# XMOS_power.net
KiCad netlist of a schematic drawn in Altium Designer
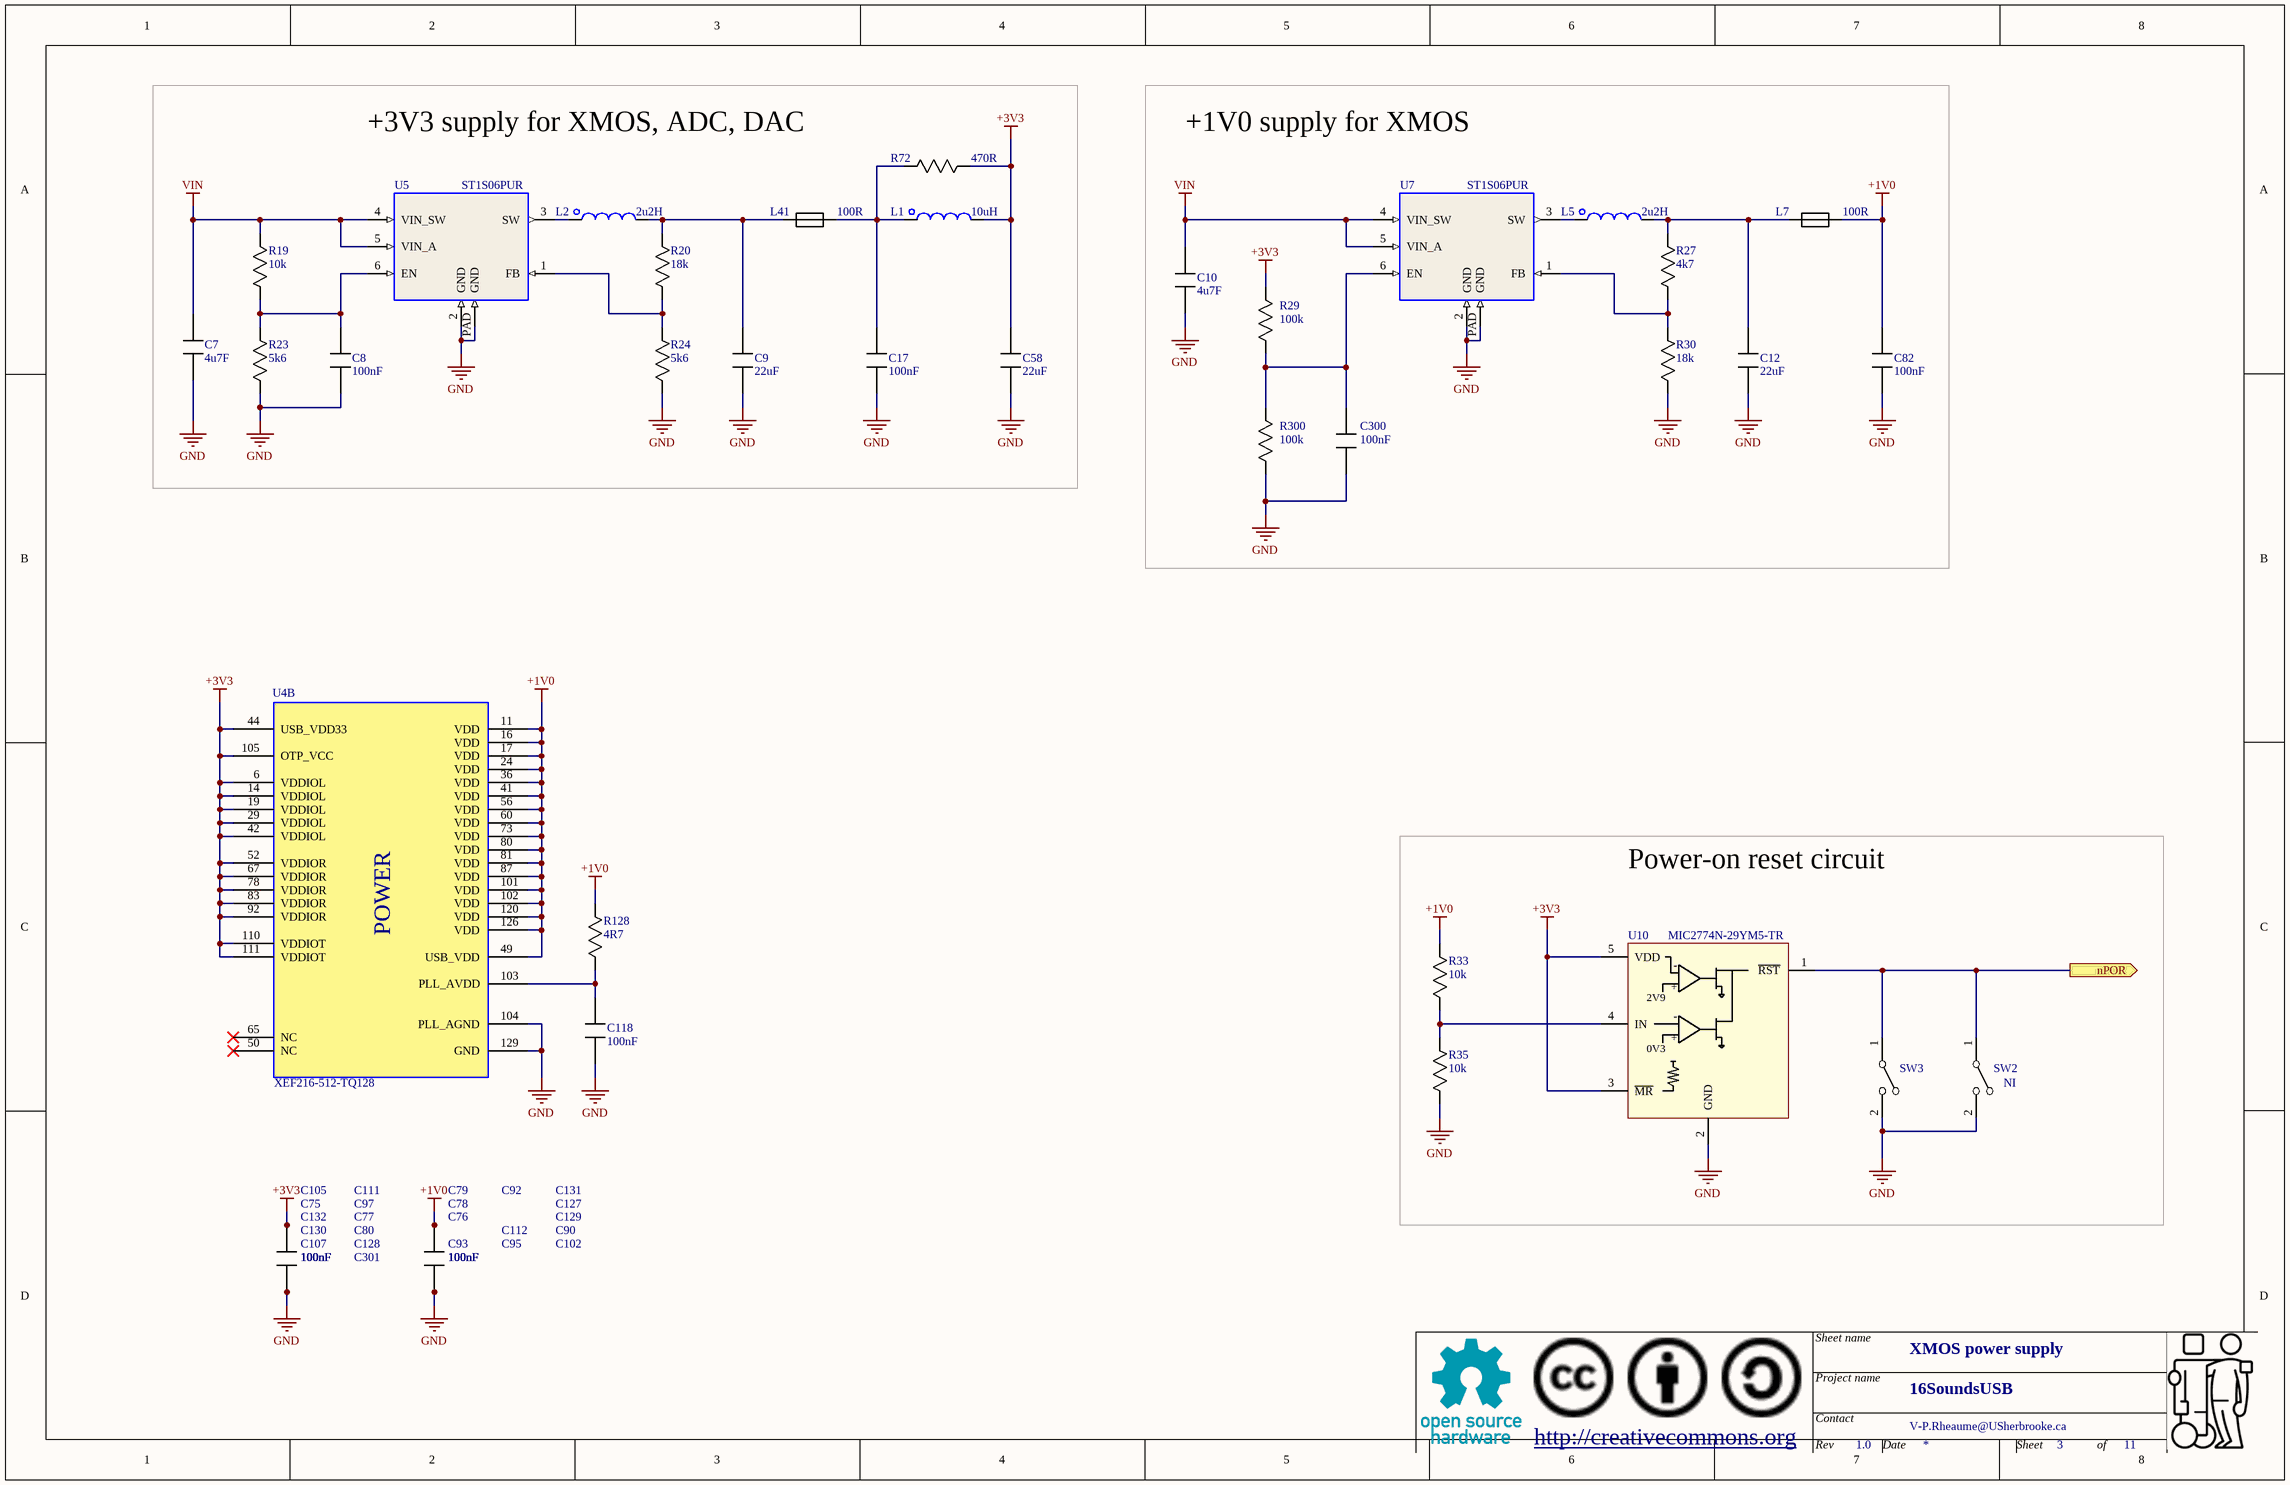
[diagram p0: XMOS_power.SchDoc]

(export (version "E")
  (design (tool "Eeschema 10.0.6"))
  (components
    (comp (ref "C7")
      (value "4u7F")
      (footprint "0805")
      (description "Capacitor")
      (libsource (lib "INTER_2014") (part "Capacitor"))
    )
    (comp (ref "C8")
      (value "100nF")
      (footprint "0603")
      (description "Capacitor")
      (libsource (lib "INTER_2014") (part "Capacitor"))
    )
    (comp (ref "C9")
      (value "22uF")
      (footprint "1206")
      (description "Capacitor")
      (libsource (lib "INTER_2014") (part "Capacitor"))
    )
    (comp (ref "C10")
      (value "4u7F")
      (footprint "0805")
      (description "Capacitor")
      (libsource (lib "INTER_2014") (part "Capacitor"))
    )
    (comp (ref "C12")
      (value "22uF")
      (footprint "1206")
      (description "Capacitor")
      (libsource (lib "INTER_2014") (part "Capacitor"))
    )
    (comp (ref "C17")
      (value "100nF")
      (footprint "0603")
      (description "Capacitor")
      (libsource (lib "INTER_2014") (part "Capacitor"))
    )
    (comp (ref "C58")
      (value "22uF")
      (footprint "1206")
      (description "Capacitor")
      (libsource (lib "INTER_2014") (part "Capacitor"))
    )
    (comp (ref "C75")
      (value "100nF")
      (footprint "0603")
      (description "Capacitor")
      (libsource (lib "INTER_2014") (part "Capacitor"))
    )
    (comp (ref "C76")
      (value "100nF")
      (footprint "0603")
      (description "Capacitor")
      (libsource (lib "INTER_2014") (part "Capacitor"))
    )
    (comp (ref "C77")
      (value "100nF")
      (footprint "0603")
      (description "Capacitor")
      (libsource (lib "INTER_2014") (part "Capacitor"))
    )
    (comp (ref "C78")
      (value "100nF")
      (footprint "0603")
      (description "Capacitor")
      (libsource (lib "INTER_2014") (part "Capacitor"))
    )
    (comp (ref "C79")
      (value "100nF")
      (footprint "0603")
      (description "Capacitor")
      (libsource (lib "INTER_2014") (part "Capacitor"))
    )
    (comp (ref "C80")
      (value "100nF")
      (footprint "0603")
      (description "Capacitor")
      (libsource (lib "INTER_2014") (part "Capacitor"))
    )
    (comp (ref "C82")
      (value "100nF")
      (footprint "0603")
      (description "Capacitor")
      (libsource (lib "INTER_2014") (part "Capacitor"))
    )
    (comp (ref "C90")
      (value "100nF")
      (footprint "0603")
      (description "Capacitor")
      (libsource (lib "INTER_2014") (part "Capacitor"))
    )
    (comp (ref "C92")
      (value "100nF")
      (footprint "0603")
      (description "Capacitor")
      (libsource (lib "INTER_2014") (part "Capacitor"))
    )
    (comp (ref "C93")
      (value "100nF")
      (footprint "0603")
      (description "Capacitor")
      (libsource (lib "INTER_2014") (part "Capacitor"))
    )
    (comp (ref "C95")
      (value "100nF")
      (footprint "0603")
      (description "Capacitor")
      (libsource (lib "INTER_2014") (part "Capacitor"))
    )
    (comp (ref "C97")
      (value "100nF")
      (footprint "0603")
      (description "Capacitor")
      (libsource (lib "INTER_2014") (part "Capacitor"))
    )
    (comp (ref "C102")
      (value "100nF")
      (footprint "0603")
      (description "Capacitor")
      (libsource (lib "INTER_2014") (part "Capacitor"))
    )
    (comp (ref "C105")
      (value "100nF")
      (footprint "0603")
      (description "Capacitor")
      (libsource (lib "INTER_2014") (part "Capacitor"))
    )
    (comp (ref "C107")
      (value "100nF")
      (footprint "0603")
      (description "Capacitor")
      (libsource (lib "INTER_2014") (part "Capacitor"))
    )
    (comp (ref "C111")
      (value "100nF")
      (footprint "0603")
      (description "Capacitor")
      (libsource (lib "INTER_2014") (part "Capacitor"))
    )
    (comp (ref "C112")
      (value "100nF")
      (footprint "0603")
      (description "Capacitor")
      (libsource (lib "INTER_2014") (part "Capacitor"))
    )
    (comp (ref "C118")
      (value "100nF")
      (footprint "0603")
      (description "Capacitor")
      (libsource (lib "INTER_2014") (part "Capacitor"))
    )
    (comp (ref "C127")
      (value "100nF")
      (footprint "0603")
      (description "Capacitor")
      (libsource (lib "INTER_2014") (part "Capacitor"))
    )
    (comp (ref "C128")
      (value "100nF")
      (footprint "0603")
      (description "Capacitor")
      (libsource (lib "INTER_2014") (part "Capacitor"))
    )
    (comp (ref "C129")
      (value "100nF")
      (footprint "0603")
      (description "Capacitor")
      (libsource (lib "INTER_2014") (part "Capacitor"))
    )
    (comp (ref "C130")
      (value "100nF")
      (footprint "0603")
      (description "Capacitor")
      (libsource (lib "INTER_2014") (part "Capacitor"))
    )
    (comp (ref "C131")
      (value "100nF")
      (footprint "0603")
      (description "Capacitor")
      (libsource (lib "INTER_2014") (part "Capacitor"))
    )
    (comp (ref "C132")
      (value "100nF")
      (footprint "0603")
      (description "Capacitor")
      (libsource (lib "INTER_2014") (part "Capacitor"))
    )
    (comp (ref "C300")
      (value "100nF")
      (footprint "0603")
      (description "Capacitor")
      (libsource (lib "INTER_2014") (part "Capacitor"))
    )
    (comp (ref "C301")
      (value "100nF")
      (footprint "0603")
      (description "Capacitor")
      (libsource (lib "INTER_2014") (part "Capacitor"))
    )
    (comp (ref "L1")
      (value "10uH")
      (footprint "IND_252012CDMC/DS")
      (description "Inductor")
      (fields (field (name "MFG") "Murata"))
      (libsource (lib "INTER_2014") (part "Inductor"))
    )
    (comp (ref "L2")
      (value "2u2H")
      (footprint "IND_252012CDMC/DS")
      (description "Inductor")
      (fields (field (name "MFG") "Murata"))
      (libsource (lib "INTER_2014") (part "Inductor"))
    )
    (comp (ref "L5")
      (value "2u2H")
      (footprint "IND_252012CDMC/DS")
      (description "Inductor")
      (fields (field (name "MFG") "Murata"))
      (libsource (lib "INTER_2014") (part "Inductor"))
    )
    (comp (ref "L7")
      (value "100R")
      (footprint "0805")
      (description "Ferrite")
      (libsource (lib "INTER_2014") (part "Ferrite"))
    )
    (comp (ref "L41")
      (value "100R")
      (footprint "0805")
      (description "Ferrite")
      (libsource (lib "INTER_2014") (part "Ferrite"))
    )
    (comp (ref "R19")
      (value "10k")
      (footprint "0603")
      (description "Resistor")
      (libsource (lib "INTER_2014") (part "Resistor"))
    )
    (comp (ref "R20")
      (value "18k")
      (footprint "0603")
      (description "Resistor")
      (libsource (lib "INTER_2014") (part "Resistor"))
    )
    (comp (ref "R23")
      (value "5k6")
      (footprint "0603")
      (description "Resistor")
      (libsource (lib "INTER_2014") (part "Resistor"))
    )
    (comp (ref "R24")
      (value "5k6")
      (footprint "0603")
      (description "Resistor")
      (libsource (lib "INTER_2014") (part "Resistor"))
    )
    (comp (ref "R27")
      (value "4k7")
      (footprint "0603")
      (description "Resistor")
      (libsource (lib "INTER_2014") (part "Resistor"))
    )
    (comp (ref "R29")
      (value "100k")
      (footprint "0603")
      (description "Resistor")
      (libsource (lib "INTER_2014") (part "Resistor"))
    )
    (comp (ref "R30")
      (value "18k")
      (footprint "0603")
      (description "Resistor")
      (libsource (lib "INTER_2014") (part "Resistor"))
    )
    (comp (ref "R33")
      (value "10k")
      (footprint "0603")
      (description "Resistor")
      (libsource (lib "INTER_2014") (part "Resistor"))
    )
    (comp (ref "R35")
      (value "10k")
      (footprint "0603")
      (description "Resistor")
      (libsource (lib "INTER_2014") (part "Resistor"))
    )
    (comp (ref "R72")
      (value "470R")
      (footprint "0603")
      (description "Resistor")
      (libsource (lib "INTER_2014") (part "Resistor"))
    )
    (comp (ref "R128")
      (value "4R7")
      (footprint "0603")
      (description "Resistor")
      (libsource (lib "INTER_2014") (part "Resistor"))
    )
    (comp (ref "R300")
      (value "100k")
      (footprint "0603")
      (description "Resistor")
      (libsource (lib "INTER_2014") (part "Resistor"))
    )
    (comp (ref "SW2")
      (value "Button")
      (footprint "BUTTON_WS-TASV")
      (fields (field (name "MFG") "Wurth") (field (name "NI") "NI"))
      (libsource (lib "INTER_2014") (part "Button"))
    )
    (comp (ref "SW3")
      (value "Button")
      (footprint "BUTTON_WS-TASV")
      (fields (field (name "MFG") "Wurth"))
      (libsource (lib "INTER_2014") (part "Button"))
    )
    (comp (ref "U4")
      (value "~")
      (footprint "TQFP128_XMOS")
      (description "32-bit multicore microcontroller. 2 Tiles. 16 Logical Cores. 512KB SRAM. 1000MIPS. TQFP128.")
      (fields (field (name "MFG") "XMOS") (field (name "MFG_PN") "XEF216-512-TQ128"))
      (libsource (lib "INTER_2014") (part "XMOS_XEF216-512-TQ128"))
    )
    (comp (ref "U5")
      (value "ST1S06PUR")
      (footprint "DFN6_ST1S06")
      (description "DC-DC Buck Converter, 1.5A, 1.5MHz, DFN6")
      (fields (field (name "MFG") "ST Microelectronics") (field (name "MFG_PN") "ST1S06PUR"))
      (libsource (lib "INTER_2014") (part "ST1S06PUR"))
    )
    (comp (ref "U7")
      (value "ST1S06PUR")
      (footprint "DFN6_ST1S06")
      (description "DC-DC Buck Converter, 1.5A, 1.5MHz, DFN6")
      (fields (field (name "MFG") "ST Microelectronics") (field (name "MFG_PN") "ST1S06PUR"))
      (libsource (lib "INTER_2014") (part "ST1S06PUR"))
    )
    (comp (ref "U10")
      (value "MIC2774N-29YM5-TR")
      (footprint "SOT23_5")
      (description "Voltage supervisor and power-on timer, dual")
      (fields (field (name "MFG") "Micrel"))
      (libsource (lib "INTER_2014") (part "MIC2774N-29YM5-TR"))
    )
  )
  (nets
    (net (code "1") (name "+1V0") (class "Default")
      (node (ref "C102") (pin "1") (pintype "passive"))
      (node (ref "C112") (pin "1") (pintype "passive"))
      (node (ref "C127") (pin "1") (pintype "passive"))
      (node (ref "C129") (pin "1") (pintype "passive"))
      (node (ref "C131") (pin "1") (pintype "passive"))
      (node (ref "C76") (pin "1") (pintype "passive"))
      (node (ref "C78") (pin "1") (pintype "passive"))
      (node (ref "C79") (pin "1") (pintype "passive"))
      (node (ref "C82") (pin "1") (pintype "passive"))
      (node (ref "C90") (pin "1") (pintype "passive"))
      (node (ref "C92") (pin "1") (pintype "passive"))
      (node (ref "C93") (pin "1") (pintype "passive"))
      (node (ref "C95") (pin "1") (pintype "passive"))
      (node (ref "L7") (pin "2") (pintype "passive"))
      (node (ref "R128") (pin "1") (pintype "passive"))
      (node (ref "R33") (pin "1") (pintype "passive"))
      (node (ref "U4") (pin "101") (pinfunction "VDD_101") (pintype "power_in"))
      (node (ref "U4") (pin "102") (pinfunction "VDD_102") (pintype "power_in"))
      (node (ref "U4") (pin "11") (pinfunction "VDD_11") (pintype "power_in"))
      (node (ref "U4") (pin "120") (pinfunction "VDD_120") (pintype "power_in"))
      (node (ref "U4") (pin "126") (pinfunction "VDD_126") (pintype "power_in"))
      (node (ref "U4") (pin "16") (pinfunction "VDD_16") (pintype "power_in"))
      (node (ref "U4") (pin "17") (pinfunction "VDD_17") (pintype "power_in"))
      (node (ref "U4") (pin "24") (pinfunction "VDD_24") (pintype "power_in"))
      (node (ref "U4") (pin "36") (pinfunction "VDD_36") (pintype "power_in"))
      (node (ref "U4") (pin "41") (pinfunction "VDD_41") (pintype "power_in"))
      (node (ref "U4") (pin "49") (pinfunction "USB_VDD_49") (pintype "power_in"))
      (node (ref "U4") (pin "56") (pinfunction "VDD_56") (pintype "power_in"))
      (node (ref "U4") (pin "60") (pinfunction "VDD_60") (pintype "power_in"))
      (node (ref "U4") (pin "73") (pinfunction "VDD_73") (pintype "power_in"))
      (node (ref "U4") (pin "80") (pinfunction "VDD_80") (pintype "power_in"))
      (node (ref "U4") (pin "81") (pinfunction "VDD_81") (pintype "power_in"))
      (node (ref "U4") (pin "87") (pinfunction "VDD_87") (pintype "power_in"))
    )
    (net (code "2") (name "+3V3") (class "Default")
      (node (ref "C105") (pin "1") (pintype "passive"))
      (node (ref "C107") (pin "1") (pintype "passive"))
      (node (ref "C111") (pin "1") (pintype "passive"))
      (node (ref "C128") (pin "1") (pintype "passive"))
      (node (ref "C130") (pin "1") (pintype "passive"))
      (node (ref "C132") (pin "1") (pintype "passive"))
      (node (ref "C301") (pin "1") (pintype "passive"))
      (node (ref "C58") (pin "1") (pintype "passive"))
      (node (ref "C75") (pin "1") (pintype "passive"))
      (node (ref "C77") (pin "1") (pintype "passive"))
      (node (ref "C80") (pin "1") (pintype "passive"))
      (node (ref "C97") (pin "1") (pintype "passive"))
      (node (ref "L1") (pin "2") (pintype "passive"))
      (node (ref "R29") (pin "1") (pintype "passive"))
      (node (ref "R72") (pin "1") (pintype "passive"))
      (node (ref "U10") (pin "3") (pinfunction "~{MR}_3") (pintype "passive"))
      (node (ref "U10") (pin "5") (pinfunction "VDD_5") (pintype "passive"))
      (node (ref "U4") (pin "105") (pinfunction "OTP_VCC_105") (pintype "power_in"))
      (node (ref "U4") (pin "110") (pinfunction "VDDIOT_110") (pintype "power_in"))
      (node (ref "U4") (pin "111") (pinfunction "VDDIOT_111") (pintype "power_in"))
      (node (ref "U4") (pin "14") (pinfunction "VDDIOL_14") (pintype "power_in"))
      (node (ref "U4") (pin "19") (pinfunction "VDDIOL_19") (pintype "power_in"))
      (node (ref "U4") (pin "29") (pinfunction "VDDIOL_29") (pintype "power_in"))
      (node (ref "U4") (pin "42") (pinfunction "VDDIOL_42") (pintype "power_in"))
      (node (ref "U4") (pin "44") (pinfunction "USB_VDD33_44") (pintype "power_in"))
      (node (ref "U4") (pin "52") (pinfunction "VDDIOR_52") (pintype "power_in"))
      (node (ref "U4") (pin "6") (pinfunction "VDDIOL_6") (pintype "power_in"))
      (node (ref "U4") (pin "67") (pinfunction "VDDIOR_67") (pintype "power_in"))
      (node (ref "U4") (pin "78") (pinfunction "VDDIOR_78") (pintype "power_in"))
      (node (ref "U4") (pin "83") (pinfunction "VDDIOR_83") (pintype "power_in"))
      (node (ref "U4") (pin "92") (pinfunction "VDDIOR_92") (pintype "power_in"))
    )
    (net (code "3") (name "/nPOR") (class "Default")
      (node (ref "SW2") (pin "1") (pintype "passive"))
      (node (ref "SW3") (pin "1") (pintype "passive"))
      (node (ref "U10") (pin "1") (pinfunction "~{RST}_1") (pintype "open_collector"))
    )
    (net (code "4") (name "GND") (class "Default")
      (node (ref "C10") (pin "2") (pintype "passive"))
      (node (ref "C102") (pin "2") (pintype "passive"))
      (node (ref "C105") (pin "2") (pintype "passive"))
      (node (ref "C107") (pin "2") (pintype "passive"))
      (node (ref "C111") (pin "2") (pintype "passive"))
      (node (ref "C112") (pin "2") (pintype "passive"))
      (node (ref "C118") (pin "2") (pintype "passive"))
      (node (ref "C12") (pin "2") (pintype "passive"))
      (node (ref "C127") (pin "2") (pintype "passive"))
      (node (ref "C128") (pin "2") (pintype "passive"))
      (node (ref "C129") (pin "2") (pintype "passive"))
      (node (ref "C130") (pin "2") (pintype "passive"))
      (node (ref "C131") (pin "2") (pintype "passive"))
      (node (ref "C132") (pin "2") (pintype "passive"))
      (node (ref "C17") (pin "2") (pintype "passive"))
      (node (ref "C300") (pin "2") (pintype "passive"))
      (node (ref "C301") (pin "2") (pintype "passive"))
      (node (ref "C58") (pin "2") (pintype "passive"))
      (node (ref "C7") (pin "2") (pintype "passive"))
      (node (ref "C75") (pin "2") (pintype "passive"))
      (node (ref "C76") (pin "2") (pintype "passive"))
      (node (ref "C77") (pin "2") (pintype "passive"))
      (node (ref "C78") (pin "2") (pintype "passive"))
      (node (ref "C79") (pin "2") (pintype "passive"))
      (node (ref "C8") (pin "2") (pintype "passive"))
      (node (ref "C80") (pin "2") (pintype "passive"))
      (node (ref "C82") (pin "2") (pintype "passive"))
      (node (ref "C9") (pin "2") (pintype "passive"))
      (node (ref "C90") (pin "2") (pintype "passive"))
      (node (ref "C92") (pin "2") (pintype "passive"))
      (node (ref "C93") (pin "2") (pintype "passive"))
      (node (ref "C95") (pin "2") (pintype "passive"))
      (node (ref "C97") (pin "2") (pintype "passive"))
      (node (ref "R23") (pin "2") (pintype "passive"))
      (node (ref "R24") (pin "2") (pintype "passive"))
      (node (ref "R30") (pin "2") (pintype "passive"))
      (node (ref "R300") (pin "2") (pintype "passive"))
      (node (ref "R35") (pin "2") (pintype "passive"))
      (node (ref "SW2") (pin "2") (pintype "passive"))
      (node (ref "SW3") (pin "2") (pintype "passive"))
      (node (ref "U10") (pin "2") (pinfunction "GND_2") (pintype "passive"))
      (node (ref "U4") (pin "104") (pinfunction "PLL_AGND_104") (pintype "power_in"))
      (node (ref "U4") (pin "129") (pinfunction "GND_129") (pintype "power_in"))
      (node (ref "U5") (pin "2") (pinfunction "GND_2") (pintype "input"))
      (node (ref "U5") (pin "PAD") (pinfunction "GND_PAD") (pintype "input"))
      (node (ref "U7") (pin "2") (pinfunction "GND_2") (pintype "input"))
      (node (ref "U7") (pin "PAD") (pinfunction "GND_PAD") (pintype "input"))
    )
    (net (code "5") (name "Net-(C9-Pad1)") (class "Default")
      (node (ref "C9") (pin "1") (pintype "passive"))
      (node (ref "L2") (pin "2") (pintype "passive"))
      (node (ref "L41") (pin "1") (pintype "passive"))
      (node (ref "R20") (pin "1") (pintype "passive"))
    )
    (net (code "6") (name "Net-(C12-Pad1)") (class "Default")
      (node (ref "C12") (pin "1") (pintype "passive"))
      (node (ref "L5") (pin "2") (pintype "passive"))
      (node (ref "L7") (pin "1") (pintype "passive"))
      (node (ref "R27") (pin "1") (pintype "passive"))
    )
    (net (code "7") (name "Net-(C17-Pad1)") (class "Default")
      (node (ref "C17") (pin "1") (pintype "passive"))
      (node (ref "L1") (pin "1") (pintype "passive"))
      (node (ref "L41") (pin "2") (pintype "passive"))
      (node (ref "R72") (pin "2") (pintype "passive"))
    )
    (net (code "8") (name "Net-(U4B-PLL_AVDD)") (class "Default")
      (node (ref "C118") (pin "1") (pintype "passive"))
      (node (ref "R128") (pin "2") (pintype "passive"))
      (node (ref "U4") (pin "103") (pinfunction "PLL_AVDD_103") (pintype "power_in"))
    )
    (net (code "9") (name "Net-(U5-EN)") (class "Default")
      (node (ref "C8") (pin "1") (pintype "passive"))
      (node (ref "R19") (pin "2") (pintype "passive"))
      (node (ref "R23") (pin "1") (pintype "passive"))
      (node (ref "U5") (pin "6") (pinfunction "EN_6") (pintype "input"))
    )
    (net (code "10") (name "Net-(U5-FB)") (class "Default")
      (node (ref "R20") (pin "2") (pintype "passive"))
      (node (ref "R24") (pin "1") (pintype "passive"))
      (node (ref "U5") (pin "1") (pinfunction "FB_1") (pintype "input"))
    )
    (net (code "11") (name "Net-(U5-SW)") (class "Default")
      (node (ref "L2") (pin "1") (pintype "passive"))
      (node (ref "U5") (pin "3") (pinfunction "SW_3") (pintype "output"))
    )
    (net (code "12") (name "Net-(U7-EN)") (class "Default")
      (node (ref "C300") (pin "1") (pintype "passive"))
      (node (ref "R29") (pin "2") (pintype "passive"))
      (node (ref "R300") (pin "1") (pintype "passive"))
      (node (ref "U7") (pin "6") (pinfunction "EN_6") (pintype "input"))
    )
    (net (code "13") (name "Net-(U7-FB)") (class "Default")
      (node (ref "R27") (pin "2") (pintype "passive"))
      (node (ref "R30") (pin "1") (pintype "passive"))
      (node (ref "U7") (pin "1") (pinfunction "FB_1") (pintype "input"))
    )
    (net (code "14") (name "Net-(U7-SW)") (class "Default")
      (node (ref "L5") (pin "1") (pintype "passive"))
      (node (ref "U7") (pin "3") (pinfunction "SW_3") (pintype "output"))
    )
    (net (code "15") (name "Net-(U10-IN)") (class "Default")
      (node (ref "R33") (pin "2") (pintype "passive"))
      (node (ref "R35") (pin "1") (pintype "passive"))
      (node (ref "U10") (pin "4") (pinfunction "IN_4") (pintype "passive"))
    )
    (net (code "16") (name "VIN") (class "Default")
      (node (ref "C10") (pin "1") (pintype "passive"))
      (node (ref "C7") (pin "1") (pintype "passive"))
      (node (ref "R19") (pin "1") (pintype "passive"))
      (node (ref "U5") (pin "4") (pinfunction "VIN_SW_4") (pintype "input"))
      (node (ref "U5") (pin "5") (pinfunction "VIN_A_5") (pintype "input"))
      (node (ref "U7") (pin "4") (pinfunction "VIN_SW_4") (pintype "input"))
      (node (ref "U7") (pin "5") (pinfunction "VIN_A_5") (pintype "input"))
    )
    (net (code "17") (name "unconnected-(SW2-Pad3)") (class "Default")
      (node (ref "SW2") (pin "3") (pintype "passive"))
    )
    (net (code "18") (name "unconnected-(SW2-Pad4)") (class "Default")
      (node (ref "SW2") (pin "4") (pintype "passive"))
    )
    (net (code "19") (name "unconnected-(SW3-Pad3)") (class "Default")
      (node (ref "SW3") (pin "3") (pintype "passive"))
    )
    (net (code "20") (name "unconnected-(SW3-Pad4)") (class "Default")
      (node (ref "SW3") (pin "4") (pintype "passive"))
    )
    (net (code "21") (name "unconnected-(U4B-NC-Pad50)") (class "Default")
      (node (ref "U4") (pin "50") (pinfunction "NC_50") (pintype "passive+no_connect"))
    )
    (net (code "22") (name "unconnected-(U4B-NC-Pad65)") (class "Default")
      (node (ref "U4") (pin "65") (pinfunction "NC_65") (pintype "passive+no_connect"))
    )
  )
)
